# supply_dual_v0_11_f04ec8e0.net
KiCad netlist of a schematic drawn in EAGLE
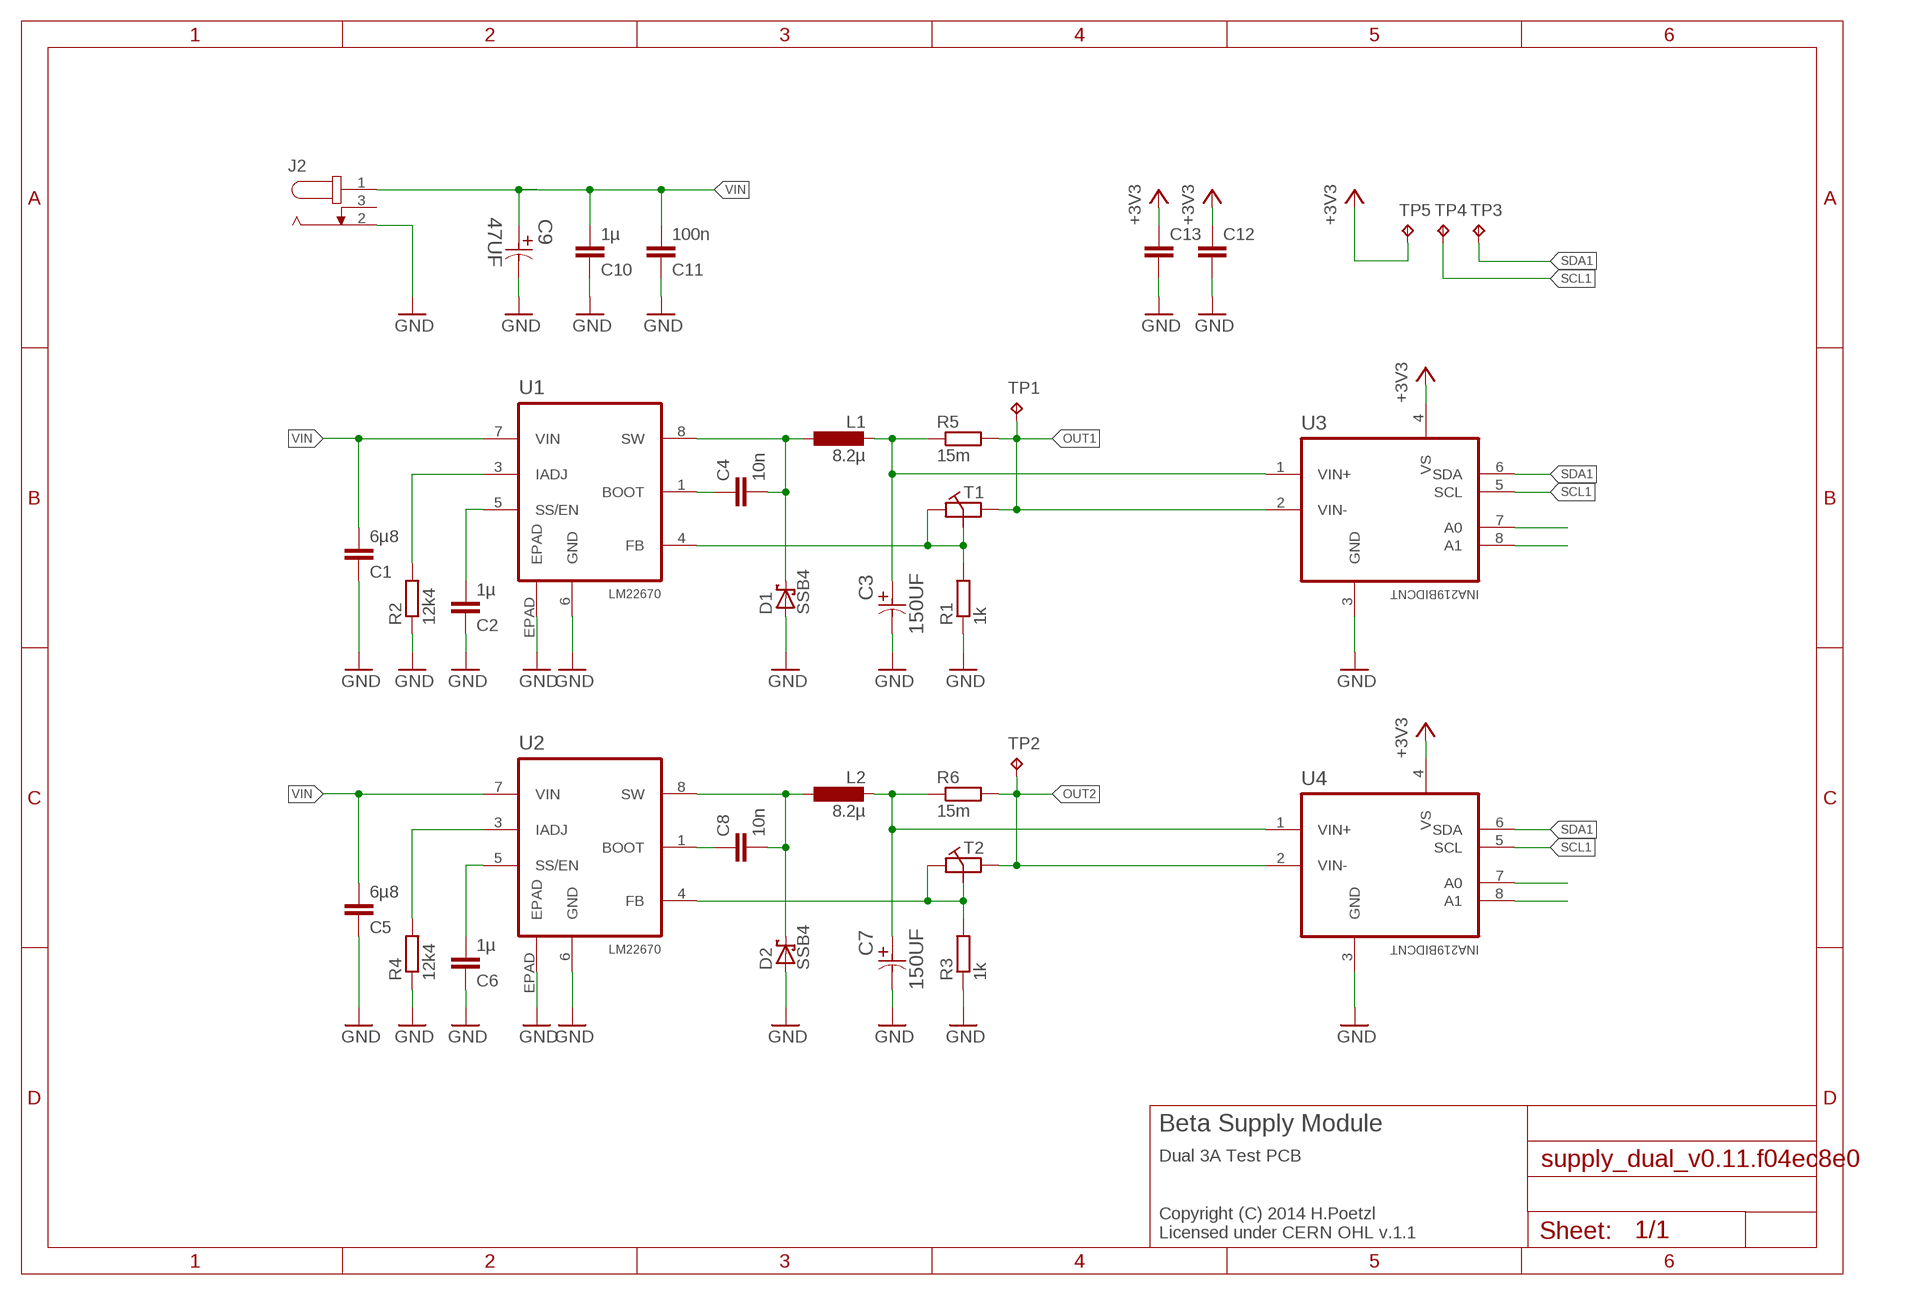
[diagram p0: schematic, sheet 1]

(export (version "E")
  (design (tool "Eeschema 10.0.6"))
  (components
    (comp (ref "C1")
      (value "6µ8")
      (footprint "eagle-import:C1210K")
      (libsource (lib "eagle-import") (part "C-EUC1210K"))
    )
    (comp (ref "C2")
      (value "1µ")
      (footprint "eagle-import:C0603K")
      (libsource (lib "eagle-import") (part "C-EUC0603K"))
    )
    (comp (ref "C3")
      (value "150UF")
      (footprint "eagle-import:CAPT7343X430N")
      (fields (field (name "MPN") "EEFCX0J151R"))
      (libsource (lib "eagle-import") (part "EEFCX0J151R"))
    )
    (comp (ref "C4")
      (value "10n")
      (footprint "eagle-import:C0603K")
      (libsource (lib "eagle-import") (part "C-EUC0603K"))
    )
    (comp (ref "C5")
      (value "6µ8")
      (footprint "eagle-import:C1210K")
      (libsource (lib "eagle-import") (part "C-EUC1210K"))
    )
    (comp (ref "C6")
      (value "1µ")
      (footprint "eagle-import:C0603K")
      (libsource (lib "eagle-import") (part "C-EUC0603K"))
    )
    (comp (ref "C7")
      (value "150UF")
      (footprint "eagle-import:CAPT7343X430N")
      (fields (field (name "MPN") "EEFCX0J151R"))
      (libsource (lib "eagle-import") (part "EEFCX0J151R"))
    )
    (comp (ref "C8")
      (value "10n")
      (footprint "eagle-import:C0603K")
      (libsource (lib "eagle-import") (part "C-EUC0603K"))
    )
    (comp (ref "C9")
      (value "47UF")
      (footprint "eagle-import:CAPAE660X610N")
      (fields (field (name "MPN") "EEE-FT1H470AP") (field (name "TOLERANCE") "±20 %"))
      (libsource (lib "eagle-import") (part "EEE--CASE-DFT1H470AP"))
    )
    (comp (ref "C10")
      (value "1µ")
      (footprint "eagle-import:C0805K")
      (libsource (lib "eagle-import") (part "C-EUC0805K"))
    )
    (comp (ref "C11")
      (value "100n")
      (footprint "eagle-import:C0603K")
      (libsource (lib "eagle-import") (part "C-EUC0603K"))
    )
    (comp (ref "C12")
      (value "C-EUC0402K")
      (footprint "eagle-import:C0402K")
      (libsource (lib "eagle-import") (part "C-EUC0402K"))
    )
    (comp (ref "C13")
      (value "C-EUC0402K")
      (footprint "eagle-import:C0402K")
      (libsource (lib "eagle-import") (part "C-EUC0402K"))
    )
    (comp (ref "D1")
      (value "SSB4")
      (footprint "eagle-import:DO-214AA")
      (libsource (lib "eagle-import") (part "SSB4"))
    )
    (comp (ref "D2")
      (value "SSB4")
      (footprint "eagle-import:DO-214AA")
      (libsource (lib "eagle-import") (part "SSB4"))
    )
    (comp (ref "J2")
      (value "JACK-PLUGDC12")
      (footprint "eagle-import:FC681485")
      (libsource (lib "eagle-import") (part "JACK-PLUGDC12"))
    )
    (comp (ref "L1")
      (value "8.2µ")
      (footprint "eagle-import:XAL50X0")
      (libsource (lib "eagle-import") (part "L-EUXAL50X0"))
    )
    (comp (ref "L2")
      (value "8.2µ")
      (footprint "eagle-import:XAL50X0")
      (libsource (lib "eagle-import") (part "L-EUXAL50X0"))
    )
    (comp (ref "R1")
      (value "1k")
      (footprint "eagle-import:R0402")
      (libsource (lib "eagle-import") (part "R-EU_R0402"))
    )
    (comp (ref "R2")
      (value "12k4")
      (footprint "eagle-import:R0402")
      (libsource (lib "eagle-import") (part "R-EU_R0402"))
    )
    (comp (ref "R3")
      (value "1k")
      (footprint "eagle-import:R0402")
      (libsource (lib "eagle-import") (part "R-EU_R0402"))
    )
    (comp (ref "R4")
      (value "12k4")
      (footprint "eagle-import:R0402")
      (libsource (lib "eagle-import") (part "R-EU_R0402"))
    )
    (comp (ref "R5")
      (value "15m")
      (footprint "eagle-import:R1210")
      (libsource (lib "eagle-import") (part "R-EU_R1210"))
    )
    (comp (ref "R6")
      (value "15m")
      (footprint "eagle-import:R1210")
      (libsource (lib "eagle-import") (part "R-EU_R1210"))
    )
    (comp (ref "T1")
      (value "PVZ2A")
      (footprint "eagle-import:TRIM-PVZ2A")
      (libsource (lib "eagle-import") (part "PVZ2A"))
    )
    (comp (ref "T2")
      (value "PVZ2A")
      (footprint "eagle-import:TRIM-PVZ2A")
      (libsource (lib "eagle-import") (part "PVZ2A"))
    )
    (comp (ref "TP1")
      (value "TPB1,27")
      (footprint "eagle-import:B1,27")
      (libsource (lib "eagle-import") (part "TPB1,27"))
    )
    (comp (ref "TP2")
      (value "TPB1,27")
      (footprint "eagle-import:B1,27")
      (libsource (lib "eagle-import") (part "TPB1,27"))
    )
    (comp (ref "TP3")
      (value "TPB1,27")
      (footprint "eagle-import:B1,27")
      (libsource (lib "eagle-import") (part "TPB1,27"))
    )
    (comp (ref "TP4")
      (value "TPB1,27")
      (footprint "eagle-import:B1,27")
      (libsource (lib "eagle-import") (part "TPB1,27"))
    )
    (comp (ref "TP5")
      (value "TPB1,27")
      (footprint "eagle-import:B1,27")
      (libsource (lib "eagle-import") (part "TPB1,27"))
    )
    (comp (ref "U1")
      (value "LM22670")
      (footprint "eagle-import:DDA0008B")
      (libsource (lib "eagle-import") (part "LM2267_123"))
    )
    (comp (ref "U2")
      (value "LM22670")
      (footprint "eagle-import:DDA0008B")
      (libsource (lib "eagle-import") (part "LM2267_123"))
    )
    (comp (ref "U3")
      (value "INA219BIDCNT")
      (footprint "eagle-import:SOT65P280X145-8N")
      (libsource (lib "eagle-import") (part "INA219BIDCNT"))
    )
    (comp (ref "U4")
      (value "INA219BIDCNT")
      (footprint "eagle-import:SOT65P280X145-8N")
      (libsource (lib "eagle-import") (part "INA219BIDCNT"))
    )
  )
  (nets
    (net (code "1") (name "+3V3") (class "Default")
      (node (ref "C12") (pin "1") (pinfunction "1_1") (pintype "passive"))
      (node (ref "C13") (pin "1") (pinfunction "1_1") (pintype "passive"))
      (node (ref "TP5") (pin "TP") (pinfunction "TP_TP") (pintype "input"))
      (node (ref "U3") (pin "4") (pinfunction "VS_4") (pintype "power_in"))
      (node (ref "U4") (pin "4") (pinfunction "VS_4") (pintype "power_in"))
    )
    (net (code "2") (name "GND") (class "Default")
      (node (ref "C1") (pin "1") (pinfunction "1_1") (pintype "passive"))
      (node (ref "C10") (pin "1") (pinfunction "1_1") (pintype "passive"))
      (node (ref "C11") (pin "1") (pinfunction "1_1") (pintype "passive"))
      (node (ref "C12") (pin "2") (pinfunction "2_2") (pintype "passive"))
      (node (ref "C13") (pin "2") (pinfunction "2_2") (pintype "passive"))
      (node (ref "C2") (pin "1") (pinfunction "1_1") (pintype "passive"))
      (node (ref "C3") (pin "2") (pinfunction "2_2") (pintype "passive"))
      (node (ref "C5") (pin "1") (pinfunction "1_1") (pintype "passive"))
      (node (ref "C6") (pin "1") (pinfunction "1_1") (pintype "passive"))
      (node (ref "C7") (pin "2") (pinfunction "2_2") (pintype "passive"))
      (node (ref "C9") (pin "2") (pinfunction "2_2") (pintype "passive"))
      (node (ref "D1") (pin "A") (pinfunction "A_A") (pintype "passive"))
      (node (ref "D2") (pin "A") (pinfunction "A_A") (pintype "passive"))
      (node (ref "J2") (pin "2") (pinfunction "2_2") (pintype "passive"))
      (node (ref "R1") (pin "1") (pinfunction "1_1") (pintype "passive"))
      (node (ref "R2") (pin "1") (pinfunction "1_1") (pintype "passive"))
      (node (ref "R3") (pin "1") (pinfunction "1_1") (pintype "passive"))
      (node (ref "R4") (pin "1") (pinfunction "1_1") (pintype "passive"))
      (node (ref "U1") (pin "6") (pinfunction "GND_6") (pintype "power_in"))
      (node (ref "U1") (pin "EPAD") (pinfunction "EPAD_EPAD") (pintype "power_in"))
      (node (ref "U2") (pin "6") (pinfunction "GND_6") (pintype "power_in"))
      (node (ref "U2") (pin "EPAD") (pinfunction "EPAD_EPAD") (pintype "power_in"))
      (node (ref "U3") (pin "3") (pinfunction "GND_3") (pintype "passive"))
      (node (ref "U4") (pin "3") (pinfunction "GND_3") (pintype "passive"))
    )
    (net (code "3") (name "Net-(T1-B)") (class "Default")
      (node (ref "R1") (pin "2") (pinfunction "2_2") (pintype "passive"))
      (node (ref "T1") (pin "2") (pinfunction "B_2") (pintype "bidirectional"))
      (node (ref "T1") (pin "3") (pinfunction "C_3") (pintype "bidirectional"))
      (node (ref "U1") (pin "4") (pinfunction "FB_4") (pintype "input"))
    )
    (net (code "4") (name "Net-(T2-B)") (class "Default")
      (node (ref "R3") (pin "2") (pinfunction "2_2") (pintype "passive"))
      (node (ref "T2") (pin "2") (pinfunction "B_2") (pintype "bidirectional"))
      (node (ref "T2") (pin "3") (pinfunction "C_3") (pintype "bidirectional"))
      (node (ref "U2") (pin "4") (pinfunction "FB_4") (pintype "input"))
    )
    (net (code "5") (name "Net-(U1-BOOT)") (class "Default")
      (node (ref "C4") (pin "1") (pinfunction "1_1") (pintype "passive"))
      (node (ref "U1") (pin "1") (pinfunction "BOOT_1") (pintype "power_in"))
    )
    (net (code "6") (name "Net-(U1-IADJ)") (class "Default")
      (node (ref "R2") (pin "2") (pinfunction "2_2") (pintype "passive"))
      (node (ref "U1") (pin "3") (pinfunction "IADJ_3") (pintype "input"))
    )
    (net (code "7") (name "Net-(U1-SS{slash}EN)") (class "Default")
      (node (ref "C2") (pin "2") (pinfunction "2_2") (pintype "passive"))
      (node (ref "U1") (pin "5") (pinfunction "SS/EN_5") (pintype "input"))
    )
    (net (code "8") (name "Net-(U1-SW)") (class "Default")
      (node (ref "C4") (pin "2") (pinfunction "2_2") (pintype "passive"))
      (node (ref "D1") (pin "C") (pinfunction "C_C") (pintype "passive"))
      (node (ref "L1") (pin "1") (pinfunction "1_1") (pintype "passive"))
      (node (ref "U1") (pin "8") (pinfunction "SW_8") (pintype "power_in"))
    )
    (net (code "9") (name "Net-(U2-BOOT)") (class "Default")
      (node (ref "C8") (pin "1") (pinfunction "1_1") (pintype "passive"))
      (node (ref "U2") (pin "1") (pinfunction "BOOT_1") (pintype "power_in"))
    )
    (net (code "10") (name "Net-(U2-IADJ)") (class "Default")
      (node (ref "R4") (pin "2") (pinfunction "2_2") (pintype "passive"))
      (node (ref "U2") (pin "3") (pinfunction "IADJ_3") (pintype "input"))
    )
    (net (code "11") (name "Net-(U2-SS{slash}EN)") (class "Default")
      (node (ref "C6") (pin "2") (pinfunction "2_2") (pintype "passive"))
      (node (ref "U2") (pin "5") (pinfunction "SS/EN_5") (pintype "input"))
    )
    (net (code "12") (name "Net-(U2-SW)") (class "Default")
      (node (ref "C8") (pin "2") (pinfunction "2_2") (pintype "passive"))
      (node (ref "D2") (pin "C") (pinfunction "C_C") (pintype "passive"))
      (node (ref "L2") (pin "1") (pinfunction "1_1") (pintype "passive"))
      (node (ref "U2") (pin "8") (pinfunction "SW_8") (pintype "power_in"))
    )
    (net (code "13") (name "Net-(U3-VIN+)") (class "Default")
      (node (ref "C3") (pin "1") (pinfunction "1_1") (pintype "passive"))
      (node (ref "L1") (pin "2") (pinfunction "2_2") (pintype "passive"))
      (node (ref "R5") (pin "1") (pinfunction "1_1") (pintype "passive"))
      (node (ref "U3") (pin "1") (pinfunction "VIN+_1") (pintype "power_in"))
    )
    (net (code "14") (name "Net-(U4-VIN+)") (class "Default")
      (node (ref "C7") (pin "1") (pinfunction "1_1") (pintype "passive"))
      (node (ref "L2") (pin "2") (pinfunction "2_2") (pintype "passive"))
      (node (ref "R6") (pin "1") (pinfunction "1_1") (pintype "passive"))
      (node (ref "U4") (pin "1") (pinfunction "VIN+_1") (pintype "power_in"))
    )
    (net (code "15") (name "OUT1") (class "Default")
      (node (ref "R5") (pin "2") (pinfunction "2_2") (pintype "passive"))
      (node (ref "T1") (pin "1") (pinfunction "A_1") (pintype "bidirectional"))
      (node (ref "TP1") (pin "TP") (pinfunction "TP_TP") (pintype "input"))
      (node (ref "U3") (pin "2") (pinfunction "VIN-_2") (pintype "power_in"))
    )
    (net (code "16") (name "OUT2") (class "Default")
      (node (ref "R6") (pin "2") (pinfunction "2_2") (pintype "passive"))
      (node (ref "T2") (pin "1") (pinfunction "A_1") (pintype "bidirectional"))
      (node (ref "TP2") (pin "TP") (pinfunction "TP_TP") (pintype "input"))
      (node (ref "U4") (pin "2") (pinfunction "VIN-_2") (pintype "power_in"))
    )
    (net (code "17") (name "SCL1") (class "Default")
      (node (ref "TP4") (pin "TP") (pinfunction "TP_TP") (pintype "input"))
      (node (ref "U3") (pin "5") (pinfunction "SCL_5") (pintype "input"))
      (node (ref "U4") (pin "5") (pinfunction "SCL_5") (pintype "input"))
    )
    (net (code "18") (name "SDA1") (class "Default")
      (node (ref "TP3") (pin "TP") (pinfunction "TP_TP") (pintype "input"))
      (node (ref "U3") (pin "6") (pinfunction "SDA_6") (pintype "bidirectional"))
      (node (ref "U4") (pin "6") (pinfunction "SDA_6") (pintype "bidirectional"))
    )
    (net (code "19") (name "VIN") (class "Default")
      (node (ref "C1") (pin "2") (pinfunction "2_2") (pintype "passive"))
      (node (ref "C10") (pin "2") (pinfunction "2_2") (pintype "passive"))
      (node (ref "C11") (pin "2") (pinfunction "2_2") (pintype "passive"))
      (node (ref "C5") (pin "2") (pinfunction "2_2") (pintype "passive"))
      (node (ref "C9") (pin "1") (pinfunction "1_1") (pintype "passive"))
      (node (ref "J2") (pin "1") (pinfunction "1_1") (pintype "passive"))
      (node (ref "U1") (pin "7") (pinfunction "VIN_7") (pintype "power_in"))
      (node (ref "U2") (pin "7") (pinfunction "VIN_7") (pintype "power_in"))
    )
    (net (code "20") (name "unconnected-(J2-Pad3)") (class "Default")
      (node (ref "J2") (pin "3") (pinfunction "3_3") (pintype "passive"))
    )
    (net (code "21") (name "unconnected-(U3-A0-Pad7)") (class "Default")
      (node (ref "U3") (pin "7") (pinfunction "A0_7") (pintype "input"))
    )
    (net (code "22") (name "unconnected-(U3-A1-Pad8)") (class "Default")
      (node (ref "U3") (pin "8") (pinfunction "A1_8") (pintype "input"))
    )
    (net (code "23") (name "unconnected-(U4-A0-Pad7)") (class "Default")
      (node (ref "U4") (pin "7") (pinfunction "A0_7") (pintype "input"))
    )
    (net (code "24") (name "unconnected-(U4-A1-Pad8)") (class "Default")
      (node (ref "U4") (pin "8") (pinfunction "A1_8") (pintype "input"))
    )
  )
)
